# Top.net
KiCad netlist of a schematic drawn in Altium Designer
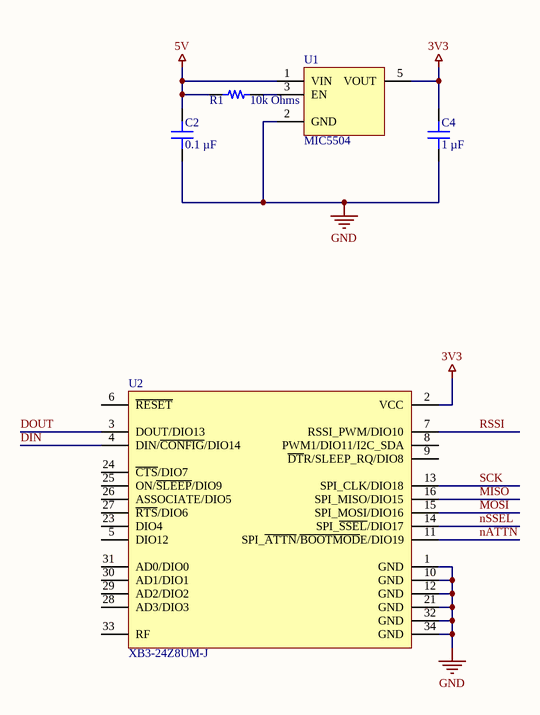
[diagram p0: Top.SchDoc]

(export (version "E")
  (design (tool "Eeschema 10.0.6"))
  (components
    (comp (ref "C2")
      (value "0.1 µF")
      (footprint "CAP 0402_1005")
      (description "CAP CER 0.1UF 16V X7R 0402")
      (fields (field (name "PART NUMBER") "C0402C104K4RACAUTO") (field (name "MANUFACTURER") "KEMET"))
      (libsource (lib "Celestial Altium Library - altium_library") (part "Capacitor"))
    )
    (comp (ref "C4")
      (value "1 µF")
      (footprint "CAP 0402_1005")
      (description "CAP CER 0.1UF 16V X7R 0402")
      (fields (field (name "PART NUMBER") "C0402C104K4RACAUTO") (field (name "MANUFACTURER") "KEMET"))
      (libsource (lib "Celestial Altium Library - altium_library") (part "Capacitor"))
    )
    (comp (ref "R1")
      (value "10k Ohms")
      (footprint "RES 0402_1005")
      (description "RES 330 OHM 5% 1/16W 0402")
      (fields (field (name "PART NUMBER") "CRCW0402330RJNEDC") (field (name "MANUFACTURER") "Vishay Dale"))
      (libsource (lib "Celestial Altium Library - altium_library") (part "Resistor"))
    )
    (comp (ref "U1")
      (value "MIC5504")
      (footprint "TI SOT-23-5 DBV")
      (description "3.3V LDO")
      (libsource (lib "IC") (part "MIC5504-3.3YM5"))
    )
    (comp (ref "U2")
      (value "XB3-24Z8UM-J")
      (footprint "XCVR_XB3-24Z8UM-J")
      (description "802.15.4 Zigbee Transceiver Module 2.4GHz Antenna Not Included, U.FL Surface Mount")
      (fields (field (name "MF") "Digi International"))
      (libsource (lib "IC") (part "XB3-24Z8UM-J"))
    )
  )
  (nets
    (net (code "1") (name "/DIN") (class "Default")
      (node (ref "U2") (pin "4") (pinfunction "DIN/~{CONFIG}/DIO14_4") (pintype "passive"))
    )
    (net (code "2") (name "/DOUT") (class "Default")
      (node (ref "U2") (pin "3") (pinfunction "DOUT/DIO13_3") (pintype "passive"))
    )
    (net (code "3") (name "/MISO") (class "Default")
      (node (ref "U2") (pin "16") (pinfunction "SPI_MISO/DIO15_16") (pintype "passive"))
    )
    (net (code "4") (name "/MOSI") (class "Default")
      (node (ref "U2") (pin "15") (pinfunction "SPI_MOSI/DIO16_15") (pintype "passive"))
    )
    (net (code "5") (name "/RSSI") (class "Default")
      (node (ref "U2") (pin "7") (pinfunction "RSSI_PWM/DIO10_7") (pintype "passive"))
    )
    (net (code "6") (name "/SCK") (class "Default")
      (node (ref "U2") (pin "13") (pinfunction "SPI_CLK/DIO18_13") (pintype "passive"))
    )
    (net (code "7") (name "/nATTN") (class "Default")
      (node (ref "U2") (pin "11") (pinfunction "SPI_~{ATTN}/~{BOOTMOD}E/DIO19_11") (pintype "passive"))
    )
    (net (code "8") (name "/nSSEL") (class "Default")
      (node (ref "U2") (pin "14") (pinfunction "SPI_~{SSEL}/DIO17_14") (pintype "passive"))
    )
    (net (code "9") (name "3V3") (class "Default")
      (node (ref "C4") (pin "2") (pinfunction "2_2") (pintype "passive"))
      (node (ref "U1") (pin "5") (pinfunction "VOUT_5") (pintype "passive"))
      (node (ref "U2") (pin "2") (pinfunction "VCC_2") (pintype "power_in"))
    )
    (net (code "10") (name "5V") (class "Default")
      (node (ref "C2") (pin "2") (pinfunction "2_2") (pintype "passive"))
      (node (ref "R1") (pin "2") (pinfunction "2_2") (pintype "passive"))
      (node (ref "U1") (pin "1") (pinfunction "VIN_1") (pintype "passive"))
    )
    (net (code "11") (name "GND") (class "Default")
      (node (ref "C2") (pin "1") (pinfunction "1_1") (pintype "passive"))
      (node (ref "C4") (pin "1") (pinfunction "1_1") (pintype "passive"))
      (node (ref "U1") (pin "2") (pinfunction "GND_2") (pintype "passive"))
      (node (ref "U2") (pin "1") (pinfunction "GND_1") (pintype "power_in"))
      (node (ref "U2") (pin "10") (pinfunction "GND_10") (pintype "power_in"))
      (node (ref "U2") (pin "12") (pinfunction "GND_12") (pintype "power_in"))
      (node (ref "U2") (pin "21") (pinfunction "GND_21") (pintype "power_in"))
      (node (ref "U2") (pin "32") (pinfunction "GND_32") (pintype "power_in"))
      (node (ref "U2") (pin "34") (pinfunction "GND_34") (pintype "power_in"))
    )
    (net (code "12") (name "Net-(U1-EN)") (class "Default")
      (node (ref "R1") (pin "1") (pinfunction "1_1") (pintype "passive"))
      (node (ref "U1") (pin "3") (pinfunction "EN_3") (pintype "passive"))
    )
    (net (code "13") (name "unconnected-(U2-AD0{slash}DIO0-Pad31)") (class "Default")
      (node (ref "U2") (pin "31") (pinfunction "AD0/DIO0_31") (pintype "passive"))
    )
    (net (code "14") (name "unconnected-(U2-AD1{slash}DIO1-Pad30)") (class "Default")
      (node (ref "U2") (pin "30") (pinfunction "AD1/DIO1_30") (pintype "passive"))
    )
    (net (code "15") (name "unconnected-(U2-AD2{slash}DIO2-Pad29)") (class "Default")
      (node (ref "U2") (pin "29") (pinfunction "AD2/DIO2_29") (pintype "passive"))
    )
    (net (code "16") (name "unconnected-(U2-AD3{slash}DIO3-Pad28)") (class "Default")
      (node (ref "U2") (pin "28") (pinfunction "AD3/DIO3_28") (pintype "passive"))
    )
    (net (code "17") (name "unconnected-(U2-ASSOCIATE{slash}DIO5-Pad26)") (class "Default")
      (node (ref "U2") (pin "26") (pinfunction "ASSOCIATE/DIO5_26") (pintype "passive"))
    )
    (net (code "18") (name "unconnected-(U2-DIO4-Pad23)") (class "Default")
      (node (ref "U2") (pin "23") (pinfunction "DIO4_23") (pintype "passive"))
    )
    (net (code "19") (name "unconnected-(U2-DIO12-Pad5)") (class "Default")
      (node (ref "U2") (pin "5") (pinfunction "DIO12_5") (pintype "passive"))
    )
    (net (code "20") (name "unconnected-(U2-ON{slash}~{SLEEP}{slash}DIO9-Pad25)") (class "Default")
      (node (ref "U2") (pin "25") (pinfunction "ON/~{SLEEP}/DIO9_25") (pintype "passive"))
    )
    (net (code "21") (name "unconnected-(U2-PWM1{slash}DIO11{slash}I2C_SDA-Pad8)") (class "Default")
      (node (ref "U2") (pin "8") (pinfunction "PWM1/DIO11/I2C_SDA_8") (pintype "passive"))
    )
    (net (code "22") (name "unconnected-(U2-RF-Pad33)") (class "Default")
      (node (ref "U2") (pin "33") (pinfunction "RF_33") (pintype "passive"))
    )
    (net (code "23") (name "unconnected-(U2-~{CTS}{slash}DIO7-Pad24)") (class "Default")
      (node (ref "U2") (pin "24") (pinfunction "~{CTS}/DIO7_24") (pintype "passive"))
    )
    (net (code "24") (name "unconnected-(U2-~{DT}R{slash}SLEEP_RQ{slash}DIO8-Pad9)") (class "Default")
      (node (ref "U2") (pin "9") (pinfunction "~{DT}R/SLEEP_RQ/DIO8_9") (pintype "passive"))
    )
    (net (code "25") (name "unconnected-(U2-~{RESET}-Pad6)") (class "Default")
      (node (ref "U2") (pin "6") (pinfunction "~{RESET}_6") (pintype "passive"))
    )
    (net (code "26") (name "unconnected-(U2-~{RTS}{slash}DIO6-Pad27)") (class "Default")
      (node (ref "U2") (pin "27") (pinfunction "~{RTS}/DIO6_27") (pintype "passive"))
    )
  )
)
